# UI-connector.net
KiCad netlist of a schematic drawn in Altium Designer
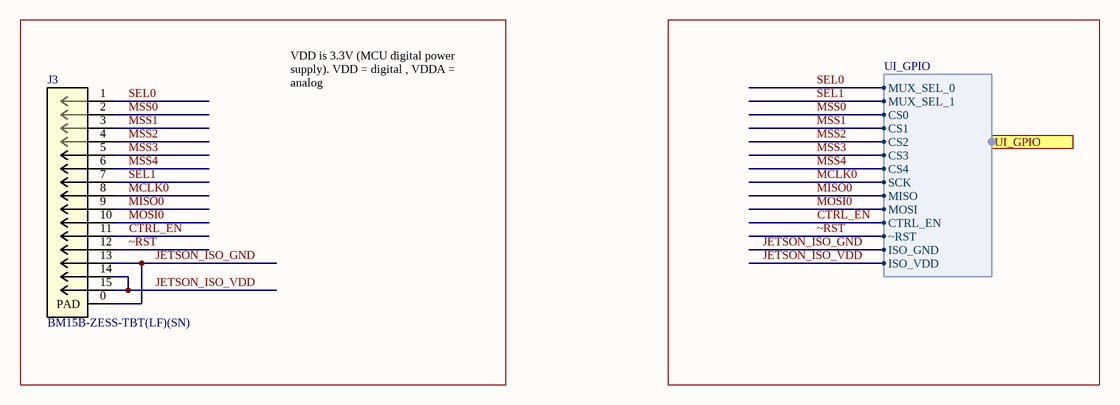
[diagram p0: UI-connector.SchDoc]

(export (version "E")
  (design (tool "Eeschema 10.0.6"))
  (components
    (comp (ref "J3")
      (value "BM15B-ZESS-TBT(LF)(SN)")
      (footprint "JST ZE SMT 15POS")
      (description "CONN HEADER VERT SMD 15POS ZE")
      (fields (field (name "PART NUMBER") "CN 15POS JST ZE SMT"))
      (libsource (lib "Connector_Library") (part "CN 15POS JST ZE SMT"))
    )
  )
  (nets
    (net (code "2") (name "/CTRL_EN") (class "Default")
      (node (ref "J3") (pin "11") (pinfunction "11_11") (pintype "passive"))
    )
    (net (code "3") (name "/JETSON_ISO_GND") (class "Default")
      (node (ref "J3") (pin "0") (pinfunction "PAD_0") (pintype "passive"))
      (node (ref "J3") (pin "13") (pinfunction "13_13") (pintype "passive"))
    )
    (net (code "4") (name "/JETSON_ISO_VDD") (class "Default")
      (node (ref "J3") (pin "14") (pinfunction "14_14") (pintype "passive"))
      (node (ref "J3") (pin "15") (pinfunction "15_15") (pintype "passive"))
    )
    (net (code "5") (name "/MCLK0") (class "Default")
      (node (ref "J3") (pin "8") (pinfunction "8_8") (pintype "passive"))
    )
    (net (code "6") (name "/MISO0") (class "Default")
      (node (ref "J3") (pin "9") (pinfunction "9_9") (pintype "passive"))
    )
    (net (code "7") (name "/MOSI0") (class "Default")
      (node (ref "J3") (pin "10") (pinfunction "10_10") (pintype "passive"))
    )
    (net (code "8") (name "/SEL0") (class "Default")
      (node (ref "J3") (pin "1") (pinfunction "1_1") (pintype "passive"))
    )
    (net (code "9") (name "/SEL1") (class "Default")
      (node (ref "J3") (pin "7") (pinfunction "7_7") (pintype "passive"))
    )
    (net (code "11") (name "/~RST") (class "Default")
      (node (ref "J3") (pin "12") (pinfunction "12_12") (pintype "passive"))
    )
    (net (code "12") (name "/~{MSS}0") (class "Default")
      (node (ref "J3") (pin "2") (pinfunction "2_2") (pintype "passive"))
    )
    (net (code "13") (name "/~{MSS}1") (class "Default")
      (node (ref "J3") (pin "3") (pinfunction "3_3") (pintype "passive"))
    )
    (net (code "14") (name "/~{MSS}2") (class "Default")
      (node (ref "J3") (pin "4") (pinfunction "4_4") (pintype "passive"))
    )
    (net (code "15") (name "/~{MSS}3") (class "Default")
      (node (ref "J3") (pin "5") (pinfunction "5_5") (pintype "passive"))
    )
    (net (code "16") (name "/~{MSS}4") (class "Default")
      (node (ref "J3") (pin "6") (pinfunction "6_6") (pintype "passive"))
    )
  )
)
